# openevse-ac-filter.net
KiCad netlist of a schematic drawn in EAGLE
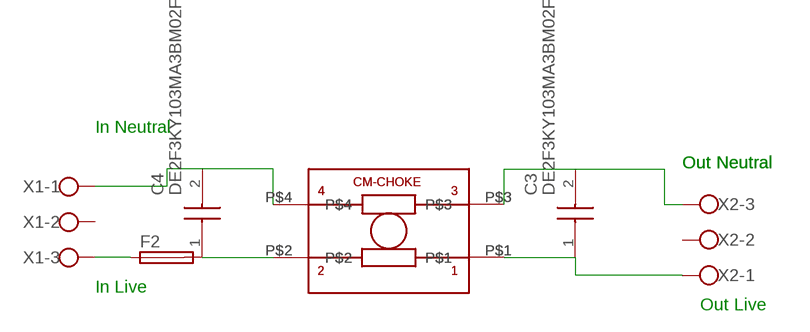
[diagram p0: schematic, sheet 1]

(export (version "E")
  (design (tool "Eeschema 10.0.6"))
  (components
    (comp (ref "C3")
      (value "DE2F3KY103MA3BM02F")
      (footprint "eagle-import:DE2F3KY103MA3BM02F")
      (fields (field (name "MOUSER_PART_NUMBER") "81-DE2F3KY103MA3BM2F"))
      (libsource (lib "eagle-import") (part "DE2F3KY103MA3BM02F"))
    )
    (comp (ref "C4")
      (value "DE2F3KY103MA3BM02F")
      (footprint "eagle-import:DE2F3KY103MA3BM02F")
      (fields (field (name "MOUSER_PART_NUMBER") "81-DE2F3KY103MA3BM2F"))
      (libsource (lib "eagle-import") (part "DE2F3KY103MA3BM02F"))
    )
    (comp (ref "F2")
      (value "GSH15")
      (footprint "eagle-import:GSH15")
      (fields (field (name "MPN") "64900001039"))
      (libsource (lib "eagle-import") (part "GSH15"))
    )
    (comp (ref "U$1")
      (value "47mH")
      (footprint "eagle-import:RN114-0.3-02-47M")
      (libsource (lib "eagle-import") (part "RN114-0.3-02-47M"))
    )
    (comp (ref "U$2")
      (value "RN214-0.3-02-47M")
      (footprint "eagle-import:RN214-0.3-02-47M")
      (libsource (lib "eagle-import") (part "RN214-0.3-02-47M"))
    )
    (comp (ref "X1")
      (value "W237-103")
      (footprint "eagle-import:W237-103")
      (fields (field (name "MPN") "237-103"))
      (libsource (lib "eagle-import") (part "W237-103"))
    )
    (comp (ref "X2")
      (value "W237-103")
      (footprint "eagle-import:W237-103")
      (fields (field (name "MPN") "237-103"))
      (libsource (lib "eagle-import") (part "W237-103"))
    )
  )
  (nets
    (net (code "1") (name "Net-(C4-Pad1)") (class "Default")
      (node (ref "C4") (pin "1") (pinfunction "1_1") (pintype "bidirectional"))
      (node (ref "F2") (pin "2") (pinfunction "2_2") (pintype "passive"))
      (node (ref "U$1") (pin "P$2") (pinfunction "P$2_P$2") (pintype "bidirectional"))
      (node (ref "U$2") (pin "P$2") (pinfunction "P$2_P$2") (pintype "bidirectional"))
    )
    (net (code "2") (name "Net-(X1A-KL)") (class "Default")
      (node (ref "C4") (pin "2") (pinfunction "2_2") (pintype "bidirectional"))
      (node (ref "U$1") (pin "P$4") (pinfunction "P$4_P$4") (pintype "bidirectional"))
      (node (ref "U$2") (pin "P$4") (pinfunction "P$4_P$4") (pintype "bidirectional"))
      (node (ref "X1") (pin "1") (pinfunction "KL_1") (pintype "passive"))
    )
    (net (code "3") (name "Net-(X1C-KL)") (class "Default")
      (node (ref "F2") (pin "1") (pinfunction "1_1") (pintype "passive"))
      (node (ref "X1") (pin "3") (pinfunction "KL_3") (pintype "passive"))
    )
    (net (code "4") (name "Net-(X2A-KL)") (class "Default")
      (node (ref "C3") (pin "1") (pinfunction "1_1") (pintype "bidirectional"))
      (node (ref "U$1") (pin "P$1") (pinfunction "P$1_P$1") (pintype "bidirectional"))
      (node (ref "U$2") (pin "P$1") (pinfunction "P$1_P$1") (pintype "bidirectional"))
      (node (ref "X2") (pin "1") (pinfunction "KL_1") (pintype "passive"))
    )
    (net (code "5") (name "Net-(X2C-KL)") (class "Default")
      (node (ref "C3") (pin "2") (pinfunction "2_2") (pintype "bidirectional"))
      (node (ref "U$1") (pin "P$3") (pinfunction "P$3_P$3") (pintype "bidirectional"))
      (node (ref "U$2") (pin "P$3") (pinfunction "P$3_P$3") (pintype "bidirectional"))
      (node (ref "X2") (pin "3") (pinfunction "KL_3") (pintype "passive"))
    )
    (net (code "6") (name "unconnected-(X1B-KL-Pad2)") (class "Default")
      (node (ref "X1") (pin "2") (pinfunction "KL_2") (pintype "passive"))
    )
    (net (code "7") (name "unconnected-(X2B-KL-Pad2)") (class "Default")
      (node (ref "X2") (pin "2") (pinfunction "KL_2") (pintype "passive"))
    )
  )
)
